# assistant.net
KiCad netlist of a schematic drawn in EAGLE
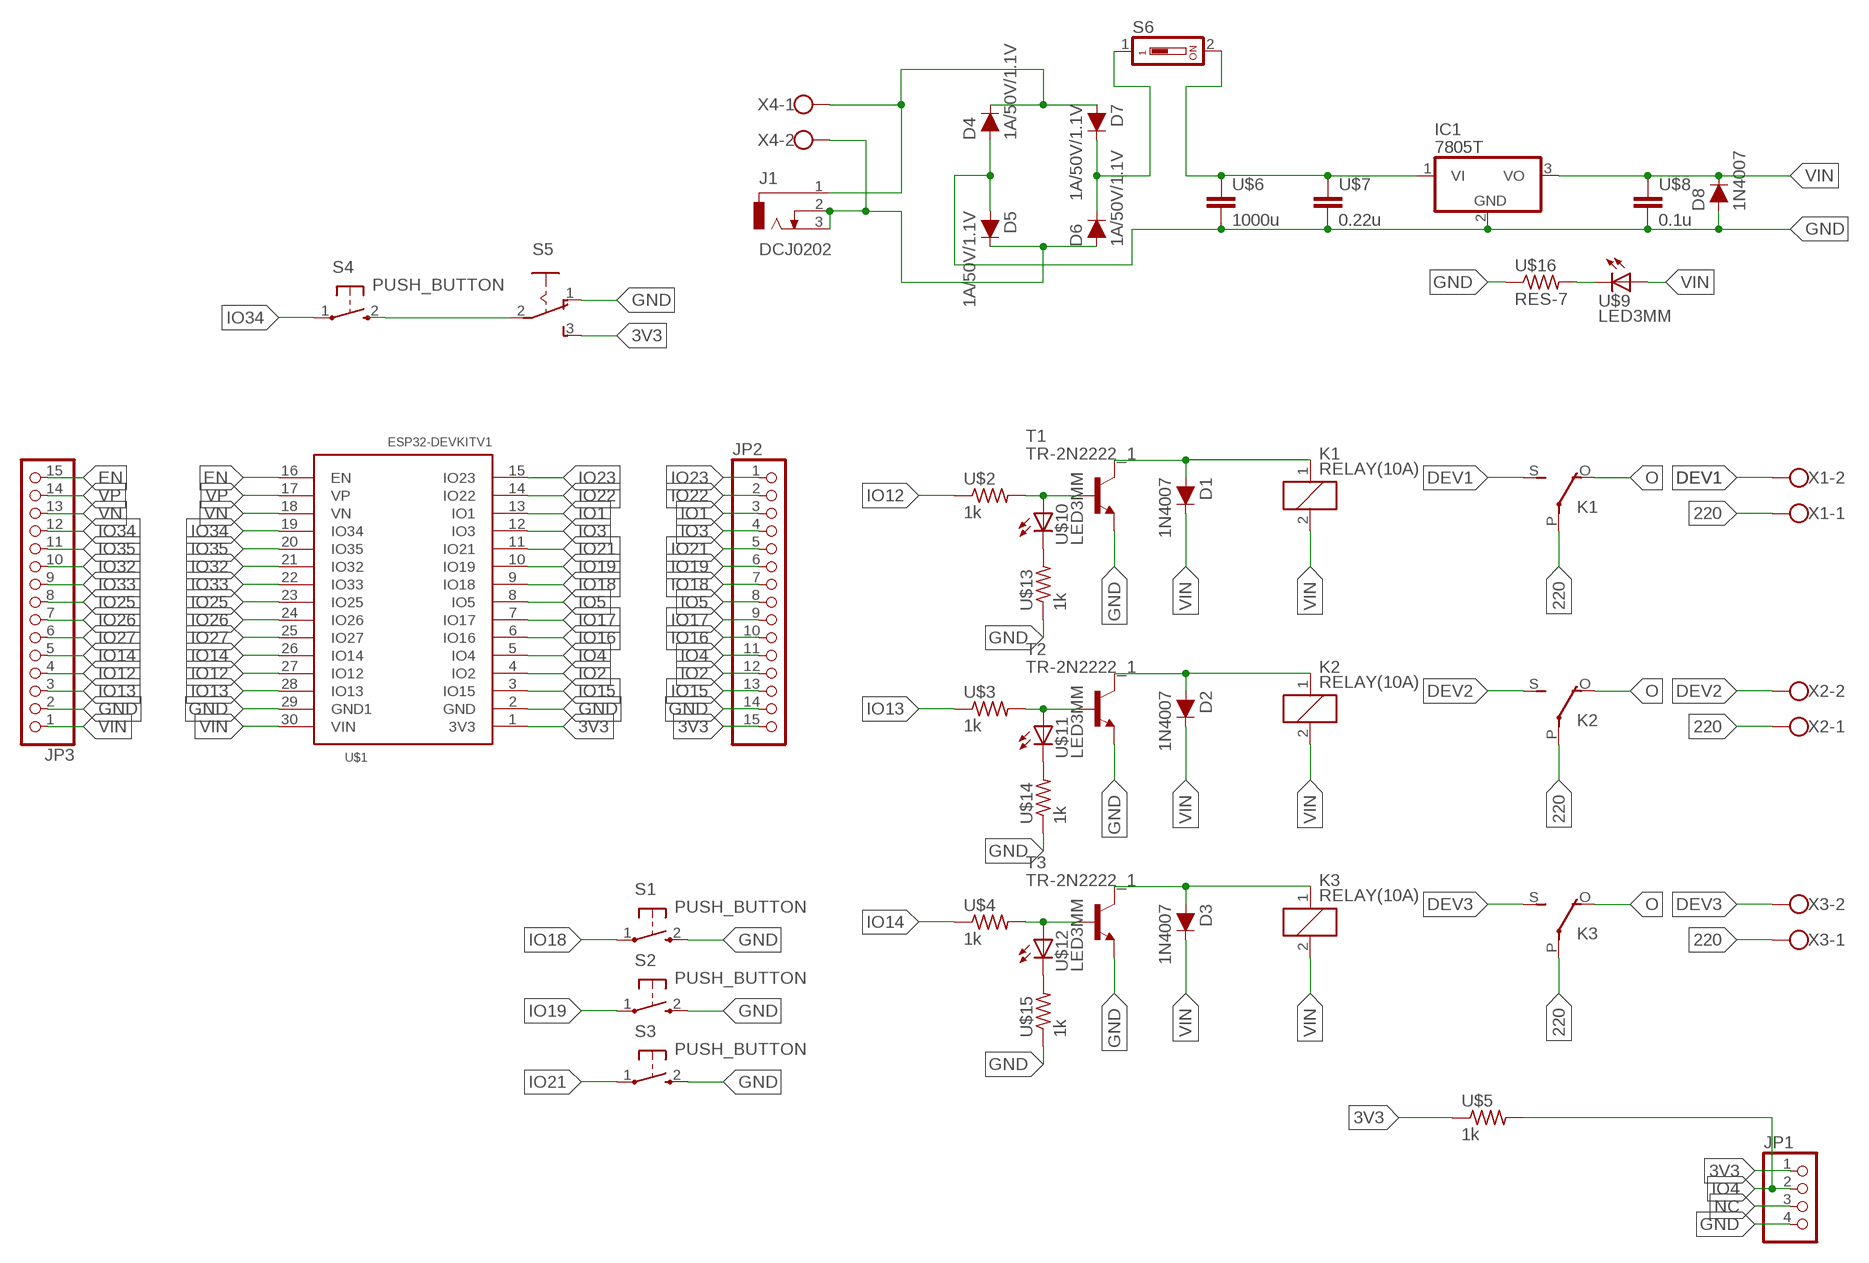
[diagram p0: schematic, sheet 1]

(export (version "E")
  (design (tool "Eeschema 10.0.6"))
  (components
    (comp (ref "D1")
      (value "1N4007")
      (footprint "eagle-import:DIODE-1N4001")
      (libsource (lib "eagle-import") (part "DIODE(1A)-PTH"))
    )
    (comp (ref "D2")
      (value "1N4007")
      (footprint "eagle-import:DIODE-1N4001")
      (libsource (lib "eagle-import") (part "DIODE(1A)-PTH"))
    )
    (comp (ref "D3")
      (value "1N4007")
      (footprint "eagle-import:DIODE-1N4001")
      (libsource (lib "eagle-import") (part "DIODE(1A)-PTH"))
    )
    (comp (ref "D4")
      (value "1A/50V/1.1V")
      (footprint "eagle-import:DIODE-1N4001")
      (libsource (lib "eagle-import") (part "DIODE(1A)-PTH"))
    )
    (comp (ref "D5")
      (value "1A/50V/1.1V")
      (footprint "eagle-import:DIODE-1N4001")
      (libsource (lib "eagle-import") (part "DIODE(1A)-PTH"))
    )
    (comp (ref "D6")
      (value "1A/50V/1.1V")
      (footprint "eagle-import:DIODE-1N4001")
      (libsource (lib "eagle-import") (part "DIODE(1A)-PTH"))
    )
    (comp (ref "D7")
      (value "1A/50V/1.1V")
      (footprint "eagle-import:DIODE-1N4001")
      (libsource (lib "eagle-import") (part "DIODE(1A)-PTH"))
    )
    (comp (ref "D8")
      (value "1N4007")
      (footprint "eagle-import:DIODE-1N4001")
      (libsource (lib "eagle-import") (part "DIODE(1A)-PTH"))
    )
    (comp (ref "IC1")
      (value "7805T")
      (footprint "eagle-import:TO220H")
      (libsource (lib "eagle-import") (part "78T05"))
    )
    (comp (ref "J1")
      (value "DCJ0202")
      (footprint "eagle-import:DCJ0202")
      (libsource (lib "eagle-import") (part "DCJ0202"))
    )
    (comp (ref "JP1")
      (value "PINHD-1X4")
      (footprint "eagle-import:1X04")
      (libsource (lib "eagle-import") (part "PINHD-1X4"))
    )
    (comp (ref "JP2")
      (value "PINHD-1X15")
      (footprint "eagle-import:1X15")
      (libsource (lib "eagle-import") (part "PINHD-1X15"))
    )
    (comp (ref "JP3")
      (value "PINHD-1X15")
      (footprint "eagle-import:1X15")
      (libsource (lib "eagle-import") (part "PINHD-1X15"))
    )
    (comp (ref "K1")
      (value "RELAY(10A)")
      (footprint "eagle-import:G5LE")
      (libsource (lib "eagle-import") (part "RELAY(10A)"))
    )
    (comp (ref "K2")
      (value "RELAY(10A)")
      (footprint "eagle-import:G5LE")
      (libsource (lib "eagle-import") (part "RELAY(10A)"))
    )
    (comp (ref "K3")
      (value "RELAY(10A)")
      (footprint "eagle-import:G5LE")
      (libsource (lib "eagle-import") (part "RELAY(10A)"))
    )
    (comp (ref "S1")
      (value "PUSH_BUTTON")
      (footprint "eagle-import:B3F-10XX")
      (libsource (lib "eagle-import") (part "PUSH_BUTTON"))
    )
    (comp (ref "S2")
      (value "PUSH_BUTTON")
      (footprint "eagle-import:B3F-10XX")
      (libsource (lib "eagle-import") (part "PUSH_BUTTON"))
    )
    (comp (ref "S3")
      (value "PUSH_BUTTON")
      (footprint "eagle-import:B3F-10XX")
      (libsource (lib "eagle-import") (part "PUSH_BUTTON"))
    )
    (comp (ref "S4")
      (value "PUSH_BUTTON")
      (footprint "eagle-import:B3F-10XX")
      (libsource (lib "eagle-import") (part "PUSH_BUTTON"))
    )
    (comp (ref "S5")
      (value "SLIDING_SWITCH")
      (footprint "eagle-import:255SB")
      (libsource (lib "eagle-import") (part "SLIDING_SWITCH"))
    )
    (comp (ref "S6")
      (value "DS01")
      (footprint "eagle-import:DS-01")
      (libsource (lib "eagle-import") (part "DS01"))
    )
    (comp (ref "T1")
      (value "TR-2N2222_1")
      (footprint "eagle-import:TO92-EBC")
      (libsource (lib "eagle-import") (part "TR-2N2222_1"))
    )
    (comp (ref "T2")
      (value "TR-2N2222_1")
      (footprint "eagle-import:TO92-EBC")
      (libsource (lib "eagle-import") (part "TR-2N2222_1"))
    )
    (comp (ref "T3")
      (value "TR-2N2222_1")
      (footprint "eagle-import:TO92-EBC")
      (libsource (lib "eagle-import") (part "TR-2N2222_1"))
    )
    (comp (ref "U$1")
      (value "ESP32DEVKITV1")
      (footprint "eagle-import:ESP32-DEVKITV1")
      (libsource (lib "eagle-import") (part "ESP32DEVKITV1"))
    )
    (comp (ref "U$2")
      (value "1k")
      (footprint "eagle-import:0204_7")
      (libsource (lib "eagle-import") (part "RES-7"))
    )
    (comp (ref "U$3")
      (value "1k")
      (footprint "eagle-import:0204_7")
      (libsource (lib "eagle-import") (part "RES-7"))
    )
    (comp (ref "U$4")
      (value "1k")
      (footprint "eagle-import:0204_7")
      (libsource (lib "eagle-import") (part "RES-7"))
    )
    (comp (ref "U$5")
      (value "1k")
      (footprint "eagle-import:0204_7")
      (libsource (lib "eagle-import") (part "RES-7"))
    )
    (comp (ref "U$6")
      (value "1000u")
      (footprint "eagle-import:C025-025X050")
      (libsource (lib "eagle-import") (part "CAPACITOR"))
    )
    (comp (ref "U$7")
      (value "0.22u")
      (footprint "eagle-import:C025-025X050")
      (libsource (lib "eagle-import") (part "CAPACITOR"))
    )
    (comp (ref "U$8")
      (value "0.1u")
      (footprint "eagle-import:C025-025X050")
      (libsource (lib "eagle-import") (part "CAPACITOR"))
    )
    (comp (ref "U$9")
      (value "LED3MM")
      (footprint "eagle-import:LED3MM")
      (libsource (lib "eagle-import") (part "LED3MM"))
    )
    (comp (ref "U$10")
      (value "LED3MM")
      (footprint "eagle-import:LED3MM")
      (libsource (lib "eagle-import") (part "LED3MM"))
    )
    (comp (ref "U$11")
      (value "LED3MM")
      (footprint "eagle-import:LED3MM")
      (libsource (lib "eagle-import") (part "LED3MM"))
    )
    (comp (ref "U$12")
      (value "LED3MM")
      (footprint "eagle-import:LED3MM")
      (libsource (lib "eagle-import") (part "LED3MM"))
    )
    (comp (ref "U$13")
      (value "1k")
      (footprint "eagle-import:0204_7")
      (libsource (lib "eagle-import") (part "RES-7"))
    )
    (comp (ref "U$14")
      (value "1k")
      (footprint "eagle-import:0204_7")
      (libsource (lib "eagle-import") (part "RES-7"))
    )
    (comp (ref "U$15")
      (value "1k")
      (footprint "eagle-import:0204_7")
      (libsource (lib "eagle-import") (part "RES-7"))
    )
    (comp (ref "U$16")
      (value "RES-7")
      (footprint "eagle-import:0204_7")
      (libsource (lib "eagle-import") (part "RES-7"))
    )
    (comp (ref "X1")
      (value "ROSTA.POWER")
      (footprint "eagle-import:W239-302")
      (libsource (lib "eagle-import") (part "ROSTA.POWER"))
    )
    (comp (ref "X2")
      (value "ROSTA.POWER")
      (footprint "eagle-import:W239-302")
      (libsource (lib "eagle-import") (part "ROSTA.POWER"))
    )
    (comp (ref "X3")
      (value "ROSTA.POWER")
      (footprint "eagle-import:W239-302")
      (libsource (lib "eagle-import") (part "ROSTA.POWER"))
    )
    (comp (ref "X4")
      (value "ROSTA.POWER")
      (footprint "eagle-import:W239-302")
      (libsource (lib "eagle-import") (part "ROSTA.POWER"))
    )
  )
  (nets
    (net (code "1") (name "3V3") (class "Default")
      (node (ref "JP1") (pin "1") (pinfunction "1_1") (pintype "passive"))
      (node (ref "JP2") (pin "15") (pinfunction "15_15") (pintype "passive"))
      (node (ref "S5") (pin "3") (pinfunction "S_3") (pintype "passive"))
      (node (ref "U$1") (pin "1") (pinfunction "3V3_1") (pintype "bidirectional"))
      (node (ref "U$5") (pin "1") (pinfunction "1_1") (pintype "passive"))
    )
    (net (code "2") (name "220") (class "Default")
      (node (ref "K1") (pin "P") (pinfunction "P_P") (pintype "passive"))
      (node (ref "K2") (pin "P") (pinfunction "P_P") (pintype "passive"))
      (node (ref "K3") (pin "P") (pinfunction "P_P") (pintype "passive"))
      (node (ref "X1") (pin "1") (pinfunction "KL_1") (pintype "passive"))
      (node (ref "X2") (pin "1") (pinfunction "KL_1") (pintype "passive"))
      (node (ref "X3") (pin "1") (pinfunction "KL_1") (pintype "passive"))
    )
    (net (code "3") (name "DEV1") (class "Default")
      (node (ref "K1") (pin "S") (pinfunction "S_S") (pintype "passive"))
      (node (ref "X1") (pin "2") (pinfunction "KL_2") (pintype "passive"))
    )
    (net (code "4") (name "DEV2") (class "Default")
      (node (ref "K2") (pin "S") (pinfunction "S_S") (pintype "passive"))
      (node (ref "X2") (pin "2") (pinfunction "KL_2") (pintype "passive"))
    )
    (net (code "5") (name "DEV3") (class "Default")
      (node (ref "K3") (pin "S") (pinfunction "S_S") (pintype "passive"))
      (node (ref "X3") (pin "2") (pinfunction "KL_2") (pintype "passive"))
    )
    (net (code "6") (name "EN") (class "Default")
      (node (ref "JP3") (pin "15") (pinfunction "15_15") (pintype "passive"))
      (node (ref "U$1") (pin "16") (pinfunction "EN_16") (pintype "bidirectional"))
    )
    (net (code "7") (name "GND") (class "Default")
      (node (ref "D4") (pin "A") (pinfunction "A_A") (pintype "passive"))
      (node (ref "D5") (pin "A") (pinfunction "A_A") (pintype "passive"))
      (node (ref "D8") (pin "A") (pinfunction "A_A") (pintype "passive"))
      (node (ref "IC1") (pin "2") (pinfunction "GND_2") (pintype "passive"))
      (node (ref "JP1") (pin "4") (pinfunction "4_4") (pintype "passive"))
      (node (ref "JP2") (pin "14") (pinfunction "14_14") (pintype "passive"))
      (node (ref "JP3") (pin "2") (pinfunction "2_2") (pintype "passive"))
      (node (ref "S1") (pin "2") (pinfunction "S_2") (pintype "passive"))
      (node (ref "S2") (pin "2") (pinfunction "S_2") (pintype "passive"))
      (node (ref "S3") (pin "2") (pinfunction "S_2") (pintype "passive"))
      (node (ref "S5") (pin "1") (pinfunction "O_1") (pintype "passive"))
      (node (ref "T1") (pin "E") (pinfunction "E_E") (pintype "passive"))
      (node (ref "T2") (pin "E") (pinfunction "E_E") (pintype "passive"))
      (node (ref "T3") (pin "E") (pinfunction "E_E") (pintype "passive"))
      (node (ref "U$1") (pin "2") (pinfunction "GND_2") (pintype "bidirectional"))
      (node (ref "U$1") (pin "29") (pinfunction "GND1_29") (pintype "bidirectional"))
      (node (ref "U$13") (pin "1") (pinfunction "1_1") (pintype "passive"))
      (node (ref "U$14") (pin "1") (pinfunction "1_1") (pintype "passive"))
      (node (ref "U$15") (pin "1") (pinfunction "1_1") (pintype "passive"))
      (node (ref "U$16") (pin "1") (pinfunction "1_1") (pintype "passive"))
      (node (ref "U$6") (pin "2") (pinfunction "2_2") (pintype "passive"))
      (node (ref "U$7") (pin "2") (pinfunction "2_2") (pintype "passive"))
      (node (ref "U$8") (pin "2") (pinfunction "2_2") (pintype "passive"))
    )
    (net (code "8") (name "IO1") (class "Default")
      (node (ref "JP2") (pin "3") (pinfunction "3_3") (pintype "passive"))
      (node (ref "U$1") (pin "13") (pinfunction "IO1_13") (pintype "bidirectional"))
    )
    (net (code "9") (name "IO2") (class "Default")
      (node (ref "JP2") (pin "12") (pinfunction "12_12") (pintype "passive"))
      (node (ref "U$1") (pin "4") (pinfunction "IO2_4") (pintype "bidirectional"))
    )
    (net (code "10") (name "IO3") (class "Default")
      (node (ref "JP2") (pin "4") (pinfunction "4_4") (pintype "passive"))
      (node (ref "U$1") (pin "12") (pinfunction "IO3_12") (pintype "bidirectional"))
    )
    (net (code "11") (name "IO4") (class "Default")
      (node (ref "JP1") (pin "2") (pinfunction "2_2") (pintype "passive"))
      (node (ref "JP2") (pin "11") (pinfunction "11_11") (pintype "passive"))
      (node (ref "U$1") (pin "5") (pinfunction "IO4_5") (pintype "bidirectional"))
      (node (ref "U$5") (pin "2") (pinfunction "2_2") (pintype "passive"))
    )
    (net (code "12") (name "IO5") (class "Default")
      (node (ref "JP2") (pin "8") (pinfunction "8_8") (pintype "passive"))
      (node (ref "U$1") (pin "8") (pinfunction "IO5_8") (pintype "bidirectional"))
    )
    (net (code "13") (name "IO12") (class "Default")
      (node (ref "JP3") (pin "4") (pinfunction "4_4") (pintype "passive"))
      (node (ref "U$1") (pin "27") (pinfunction "IO12_27") (pintype "bidirectional"))
      (node (ref "U$2") (pin "1") (pinfunction "1_1") (pintype "passive"))
    )
    (net (code "14") (name "IO13") (class "Default")
      (node (ref "JP3") (pin "3") (pinfunction "3_3") (pintype "passive"))
      (node (ref "U$1") (pin "28") (pinfunction "IO13_28") (pintype "bidirectional"))
      (node (ref "U$3") (pin "1") (pinfunction "1_1") (pintype "passive"))
    )
    (net (code "15") (name "IO14") (class "Default")
      (node (ref "JP3") (pin "5") (pinfunction "5_5") (pintype "passive"))
      (node (ref "U$1") (pin "26") (pinfunction "IO14_26") (pintype "bidirectional"))
      (node (ref "U$4") (pin "1") (pinfunction "1_1") (pintype "passive"))
    )
    (net (code "16") (name "IO15") (class "Default")
      (node (ref "JP2") (pin "13") (pinfunction "13_13") (pintype "passive"))
      (node (ref "U$1") (pin "3") (pinfunction "IO15_3") (pintype "bidirectional"))
    )
    (net (code "17") (name "IO16") (class "Default")
      (node (ref "JP2") (pin "10") (pinfunction "10_10") (pintype "passive"))
      (node (ref "U$1") (pin "6") (pinfunction "IO16_6") (pintype "bidirectional"))
    )
    (net (code "18") (name "IO17") (class "Default")
      (node (ref "JP2") (pin "9") (pinfunction "9_9") (pintype "passive"))
      (node (ref "U$1") (pin "7") (pinfunction "IO17_7") (pintype "bidirectional"))
    )
    (net (code "19") (name "IO18") (class "Default")
      (node (ref "JP2") (pin "7") (pinfunction "7_7") (pintype "passive"))
      (node (ref "S1") (pin "1") (pinfunction "P_1") (pintype "passive"))
      (node (ref "U$1") (pin "9") (pinfunction "IO18_9") (pintype "bidirectional"))
    )
    (net (code "20") (name "IO19") (class "Default")
      (node (ref "JP2") (pin "6") (pinfunction "6_6") (pintype "passive"))
      (node (ref "S2") (pin "1") (pinfunction "P_1") (pintype "passive"))
      (node (ref "U$1") (pin "10") (pinfunction "IO19_10") (pintype "bidirectional"))
    )
    (net (code "21") (name "IO21") (class "Default")
      (node (ref "JP2") (pin "5") (pinfunction "5_5") (pintype "passive"))
      (node (ref "S3") (pin "1") (pinfunction "P_1") (pintype "passive"))
      (node (ref "U$1") (pin "11") (pinfunction "IO21_11") (pintype "bidirectional"))
    )
    (net (code "22") (name "IO22") (class "Default")
      (node (ref "JP2") (pin "2") (pinfunction "2_2") (pintype "passive"))
      (node (ref "U$1") (pin "14") (pinfunction "IO22_14") (pintype "bidirectional"))
    )
    (net (code "23") (name "IO23") (class "Default")
      (node (ref "JP2") (pin "1") (pinfunction "1_1") (pintype "passive"))
      (node (ref "U$1") (pin "15") (pinfunction "IO23_15") (pintype "bidirectional"))
    )
    (net (code "24") (name "IO25") (class "Default")
      (node (ref "JP3") (pin "8") (pinfunction "8_8") (pintype "passive"))
      (node (ref "U$1") (pin "23") (pinfunction "IO25_23") (pintype "bidirectional"))
    )
    (net (code "25") (name "IO26") (class "Default")
      (node (ref "JP3") (pin "7") (pinfunction "7_7") (pintype "passive"))
      (node (ref "U$1") (pin "24") (pinfunction "IO26_24") (pintype "bidirectional"))
    )
    (net (code "26") (name "IO27") (class "Default")
      (node (ref "JP3") (pin "6") (pinfunction "6_6") (pintype "passive"))
      (node (ref "U$1") (pin "25") (pinfunction "IO27_25") (pintype "bidirectional"))
    )
    (net (code "27") (name "IO32") (class "Default")
      (node (ref "JP3") (pin "10") (pinfunction "10_10") (pintype "passive"))
      (node (ref "U$1") (pin "21") (pinfunction "IO32_21") (pintype "bidirectional"))
    )
    (net (code "28") (name "IO33") (class "Default")
      (node (ref "JP3") (pin "9") (pinfunction "9_9") (pintype "passive"))
      (node (ref "U$1") (pin "22") (pinfunction "IO33_22") (pintype "bidirectional"))
    )
    (net (code "29") (name "IO34") (class "Default")
      (node (ref "JP3") (pin "12") (pinfunction "12_12") (pintype "passive"))
      (node (ref "S4") (pin "1") (pinfunction "P_1") (pintype "passive"))
      (node (ref "U$1") (pin "19") (pinfunction "IO34_19") (pintype "bidirectional"))
    )
    (net (code "30") (name "IO35") (class "Default")
      (node (ref "JP3") (pin "11") (pinfunction "11_11") (pintype "passive"))
      (node (ref "U$1") (pin "20") (pinfunction "IO35_20") (pintype "bidirectional"))
    )
    (net (code "31") (name "NC") (class "Default")
      (node (ref "JP1") (pin "3") (pinfunction "3_3") (pintype "passive"))
    )
    (net (code "32") (name "Net-(D1-PadA)") (class "Default")
      (node (ref "D1") (pin "A") (pinfunction "A_A") (pintype "passive"))
      (node (ref "K1") (pin "1") (pinfunction "1_1") (pintype "passive"))
      (node (ref "T1") (pin "C") (pinfunction "C_C") (pintype "passive"))
    )
    (net (code "33") (name "Net-(D2-PadA)") (class "Default")
      (node (ref "D2") (pin "A") (pinfunction "A_A") (pintype "passive"))
      (node (ref "K2") (pin "1") (pinfunction "1_1") (pintype "passive"))
      (node (ref "T2") (pin "C") (pinfunction "C_C") (pintype "passive"))
    )
    (net (code "34") (name "Net-(D3-PadA)") (class "Default")
      (node (ref "D3") (pin "A") (pinfunction "A_A") (pintype "passive"))
      (node (ref "K3") (pin "1") (pinfunction "1_1") (pintype "passive"))
      (node (ref "T3") (pin "C") (pinfunction "C_C") (pintype "passive"))
    )
    (net (code "35") (name "Net-(D6-PadC)") (class "Default")
      (node (ref "D6") (pin "C") (pinfunction "C_C") (pintype "passive"))
      (node (ref "D7") (pin "C") (pinfunction "C_C") (pintype "passive"))
      (node (ref "S6") (pin "1") (pinfunction "1_1") (pintype "passive"))
    )
    (net (code "36") (name "Net-(IC1-VI)") (class "Default")
      (node (ref "IC1") (pin "1") (pinfunction "VI_1") (pintype "input"))
      (node (ref "S6") (pin "2") (pinfunction "2_2") (pintype "passive"))
      (node (ref "U$6") (pin "1") (pinfunction "1_1") (pintype "passive"))
      (node (ref "U$7") (pin "1") (pinfunction "1_1") (pintype "passive"))
    )
    (net (code "37") (name "Net-(S4-S)") (class "Default")
      (node (ref "S4") (pin "2") (pinfunction "S_2") (pintype "passive"))
      (node (ref "S5") (pin "2") (pinfunction "P_2") (pintype "passive"))
    )
    (net (code "38") (name "Net-(T1-PadB)") (class "Default")
      (node (ref "T1") (pin "B") (pinfunction "B_B") (pintype "passive"))
      (node (ref "U$10") (pin "A") (pinfunction "A_A") (pintype "passive"))
      (node (ref "U$2") (pin "2") (pinfunction "2_2") (pintype "passive"))
    )
    (net (code "39") (name "Net-(T2-PadB)") (class "Default")
      (node (ref "T2") (pin "B") (pinfunction "B_B") (pintype "passive"))
      (node (ref "U$11") (pin "A") (pinfunction "A_A") (pintype "passive"))
      (node (ref "U$3") (pin "2") (pinfunction "2_2") (pintype "passive"))
    )
    (net (code "40") (name "Net-(T3-PadB)") (class "Default")
      (node (ref "T3") (pin "B") (pinfunction "B_B") (pintype "passive"))
      (node (ref "U$12") (pin "A") (pinfunction "A_A") (pintype "passive"))
      (node (ref "U$4") (pin "2") (pinfunction "2_2") (pintype "passive"))
    )
    (net (code "41") (name "Net-(U$9-C)") (class "Default")
      (node (ref "U$16") (pin "2") (pinfunction "2_2") (pintype "passive"))
      (node (ref "U$9") (pin "K") (pinfunction "C_K") (pintype "passive"))
    )
    (net (code "42") (name "Net-(U$10-C)") (class "Default")
      (node (ref "U$10") (pin "K") (pinfunction "C_K") (pintype "passive"))
      (node (ref "U$13") (pin "2") (pinfunction "2_2") (pintype "passive"))
    )
    (net (code "43") (name "Net-(U$11-C)") (class "Default")
      (node (ref "U$11") (pin "K") (pinfunction "C_K") (pintype "passive"))
      (node (ref "U$14") (pin "2") (pinfunction "2_2") (pintype "passive"))
    )
    (net (code "44") (name "Net-(U$12-C)") (class "Default")
      (node (ref "U$12") (pin "K") (pinfunction "C_K") (pintype "passive"))
      (node (ref "U$15") (pin "2") (pinfunction "2_2") (pintype "passive"))
    )
    (net (code "45") (name "Net-(X4A-KL)") (class "Default")
      (node (ref "D4") (pin "C") (pinfunction "C_C") (pintype "passive"))
      (node (ref "D7") (pin "A") (pinfunction "A_A") (pintype "passive"))
      (node (ref "J1") (pin "1") (pinfunction "1_1") (pintype "passive"))
      (node (ref "X4") (pin "1") (pinfunction "KL_1") (pintype "passive"))
    )
    (net (code "46") (name "Net-(X4B-KL)") (class "Default")
      (node (ref "D5") (pin "C") (pinfunction "C_C") (pintype "passive"))
      (node (ref "D6") (pin "A") (pinfunction "A_A") (pintype "passive"))
      (node (ref "J1") (pin "2") (pinfunction "2_2") (pintype "passive"))
      (node (ref "J1") (pin "3") (pinfunction "3_3") (pintype "passive"))
      (node (ref "X4") (pin "2") (pinfunction "KL_2") (pintype "passive"))
    )
    (net (code "47") (name "O") (class "Default")
      (node (ref "K1") (pin "O") (pinfunction "O_O") (pintype "passive"))
      (node (ref "K2") (pin "O") (pinfunction "O_O") (pintype "passive"))
      (node (ref "K3") (pin "O") (pinfunction "O_O") (pintype "passive"))
    )
    (net (code "48") (name "VIN") (class "Default")
      (node (ref "D1") (pin "C") (pinfunction "C_C") (pintype "passive"))
      (node (ref "D2") (pin "C") (pinfunction "C_C") (pintype "passive"))
      (node (ref "D3") (pin "C") (pinfunction "C_C") (pintype "passive"))
      (node (ref "D8") (pin "C") (pinfunction "C_C") (pintype "passive"))
      (node (ref "IC1") (pin "3") (pinfunction "VO_3") (pintype "passive"))
      (node (ref "JP3") (pin "1") (pinfunction "1_1") (pintype "passive"))
      (node (ref "K1") (pin "2") (pinfunction "2_2") (pintype "passive"))
      (node (ref "K2") (pin "2") (pinfunction "2_2") (pintype "passive"))
      (node (ref "K3") (pin "2") (pinfunction "2_2") (pintype "passive"))
      (node (ref "U$1") (pin "30") (pinfunction "VIN_30") (pintype "bidirectional"))
      (node (ref "U$8") (pin "1") (pinfunction "1_1") (pintype "passive"))
      (node (ref "U$9") (pin "A") (pinfunction "A_A") (pintype "passive"))
    )
    (net (code "49") (name "VN") (class "Default")
      (node (ref "JP3") (pin "13") (pinfunction "13_13") (pintype "passive"))
      (node (ref "U$1") (pin "18") (pinfunction "VN_18") (pintype "bidirectional"))
    )
    (net (code "50") (name "VP") (class "Default")
      (node (ref "JP3") (pin "14") (pinfunction "14_14") (pintype "passive"))
      (node (ref "U$1") (pin "17") (pinfunction "VP_17") (pintype "bidirectional"))
    )
  )
)
